# 13_ACODEC.net
KiCad netlist of a schematic drawn in Altium Designer
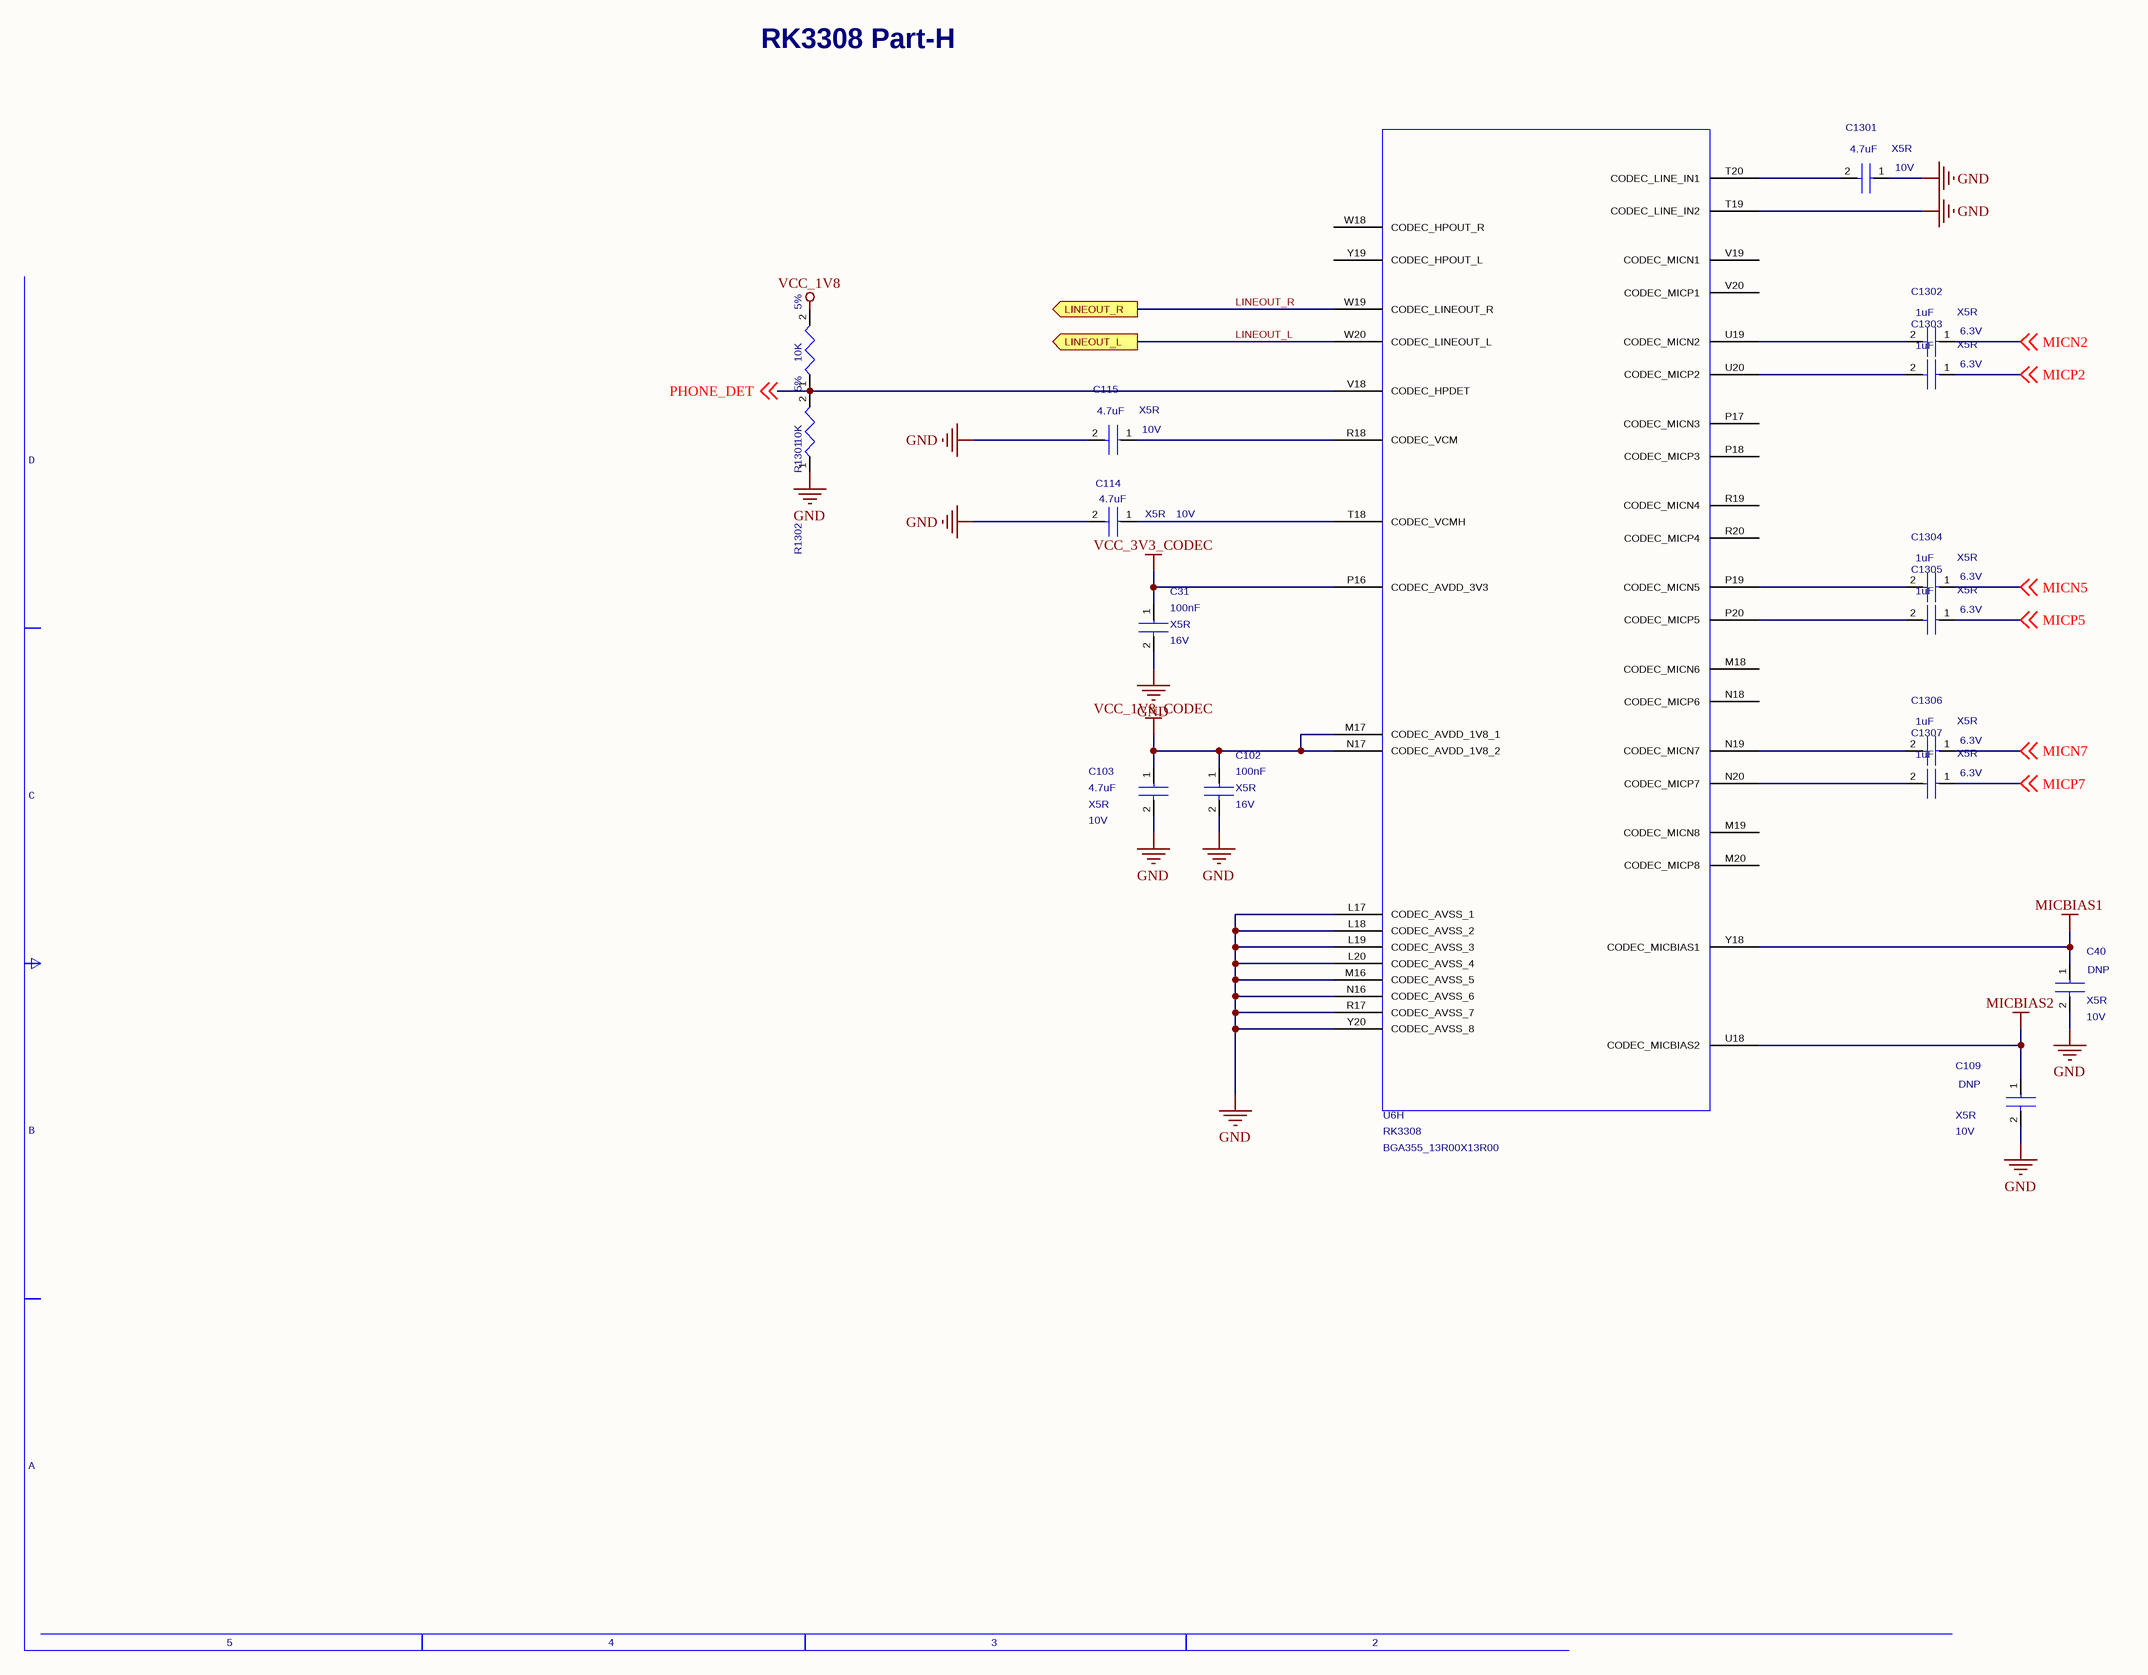
[diagram p0: 13_ACODEC.SchDoc]

(export (version "E")
  (design (tool "Eeschema 10.0.6"))
  (components
    (comp (ref "C31")
      (value "100nF")
      (footprint "C0402")
      (description "cap,100.00nF,+/-10%,16V,X5R,C0402")
      (fields
        (field (name "MANUFACTURER") "TDK")
        (field (name "TOLERANCE") "10%")
        (field (name "VOLTAGE") "16V")
        (field (name "DIELECTRIC") "X5R")
        (field (name "CREATED_BY") "JJJ")
      )
      (libsource (lib "*") (part "CAP_NP_2"))
    )
    (comp (ref "C40")
      (value "CAP_NP_2")
      (footprint "C0402")
      (description "cap,1.00uF,+/-10%,10V,X5R,C0402")
      (fields
        (field (name "DIELECTRIC") "X5R")
        (field (name "VOLTAGE") "10V")
        (field (name "TOLERANCE") "10%")
        (field (name "MANUFACTURER") "TDK")
        (field (name "OPTION") "DNP")
        (field (name "CREATED_BY") "JJJ")
      )
      (libsource (lib "*") (part "CAP_NP_2"))
    )
    (comp (ref "C102")
      (value "100nF")
      (footprint "C0402")
      (description "cap,100.00nF,+/-10%,16V,X5R,C0402")
      (fields
        (field (name "DIELECTRIC") "X5R")
        (field (name "VOLTAGE") "16V")
        (field (name "TOLERANCE") "10%")
        (field (name "MANUFACTURER") "TDK")
        (field (name "CREATED_BY") "JJJ")
      )
      (libsource (lib "*") (part "CAP_NP_2"))
    )
    (comp (ref "C103")
      (value "4.7uF")
      (footprint "C0402")
      (description "cap,4.70uF,+/-10%,10V,X5R,C0402")
      (fields
        (field (name "DIELECTRIC") "X5R")
        (field (name "VOLTAGE") "10V")
        (field (name "TOLERANCE") "10%")
        (field (name "MANUFACTURER") "TDK")
        (field (name "CREATED_BY") "JJJ")
      )
      (libsource (lib "*") (part "CAP_NP_2"))
    )
    (comp (ref "C109")
      (value "CAP_NP_2")
      (footprint "C0402")
      (description "cap,1.00uF,+/-10%,10V,X5R,C0402")
      (fields
        (field (name "MANUFACTURER") "TDK")
        (field (name "TOLERANCE") "10%")
        (field (name "VOLTAGE") "10V")
        (field (name "DIELECTRIC") "X5R")
        (field (name "OPTION") "DNP")
        (field (name "CREATED_BY") "JJJ")
      )
      (libsource (lib "*") (part "CAP_NP_2"))
    )
    (comp (ref "C114")
      (value "4.7uF")
      (footprint "C0603")
      (description "cap,4.70uF,+/-10%,10V,X5R,C0603")
      (fields
        (field (name "MANUFACTURER") "TDK")
        (field (name "TOLERANCE") "10%")
        (field (name "VOLTAGE") "10V")
        (field (name "DIELECTRIC") "X5R")
        (field (name "CREATED_BY") "JJJ")
      )
      (libsource (lib "*") (part "CAP_NP_2"))
    )
    (comp (ref "C115")
      (value "4.7uF")
      (footprint "C0603")
      (description "cap,4.70uF,+/-10%,10V,X5R,C0603")
      (fields
        (field (name "MANUFACTURER") "TDK")
        (field (name "TOLERANCE") "10%")
        (field (name "VOLTAGE") "10V")
        (field (name "DIELECTRIC") "X5R")
        (field (name "CREATED_BY") "JJJ")
      )
      (libsource (lib "*") (part "CAP_NP_2"))
    )
    (comp (ref "C1301")
      (value "4.7uF")
      (footprint "C0603")
      (description "cap,4.70uF,+/-10%,10V,X5R,C0603")
      (fields
        (field (name "MANUFACTURER") "TDK")
        (field (name "TOLERANCE") "10%")
        (field (name "VOLTAGE") "10V")
        (field (name "DIELECTRIC") "X5R")
        (field (name "CREATED_BY") "JJJ")
      )
      (libsource (lib "*") (part "CAP_NP_2"))
    )
    (comp (ref "C1302")
      (value "1uF")
      (footprint "C0402")
      (description "cap,1uF,+/-10%,10V,X5R,C0402")
      (fields
        (field (name "MANUFACTURER") "TDK")
        (field (name "TOLERANCE") "10%")
        (field (name "VOLTAGE") "6.3V")
        (field (name "DIELECTRIC") "X5R")
        (field (name "CREATED_BY") "JJJ")
      )
      (libsource (lib "*") (part "CAP_NP_2"))
    )
    (comp (ref "C1303")
      (value "1uF")
      (footprint "C0402")
      (description "cap,1uF,+/-10%,10V,X5R,C0402")
      (fields
        (field (name "MANUFACTURER") "TDK")
        (field (name "TOLERANCE") "10%")
        (field (name "VOLTAGE") "6.3V")
        (field (name "DIELECTRIC") "X5R")
        (field (name "CREATED_BY") "JJJ")
      )
      (libsource (lib "*") (part "CAP_NP_2"))
    )
    (comp (ref "C1304")
      (value "1uF")
      (footprint "C0402")
      (description "cap,1uF,+/-10%,10V,X5R,C0402")
      (fields
        (field (name "MANUFACTURER") "TDK")
        (field (name "TOLERANCE") "10%")
        (field (name "VOLTAGE") "6.3V")
        (field (name "DIELECTRIC") "X5R")
        (field (name "CREATED_BY") "JJJ")
      )
      (libsource (lib "*") (part "CAP_NP_2"))
    )
    (comp (ref "C1305")
      (value "1uF")
      (footprint "C0402")
      (description "cap,1uF,+/-10%,10V,X5R,C0402")
      (fields
        (field (name "MANUFACTURER") "TDK")
        (field (name "TOLERANCE") "10%")
        (field (name "VOLTAGE") "6.3V")
        (field (name "DIELECTRIC") "X5R")
        (field (name "CREATED_BY") "JJJ")
      )
      (libsource (lib "*") (part "CAP_NP_2"))
    )
    (comp (ref "C1306")
      (value "1uF")
      (footprint "C0402")
      (description "cap,1uF,+/-10%,10V,X5R,C0402")
      (fields
        (field (name "MANUFACTURER") "TDK")
        (field (name "TOLERANCE") "10%")
        (field (name "VOLTAGE") "6.3V")
        (field (name "DIELECTRIC") "X5R")
        (field (name "CREATED_BY") "JJJ")
      )
      (libsource (lib "*") (part "CAP_NP_2"))
    )
    (comp (ref "C1307")
      (value "1uF")
      (footprint "C0402")
      (description "cap,1uF,+/-10%,10V,X5R,C0402")
      (fields
        (field (name "MANUFACTURER") "TDK")
        (field (name "TOLERANCE") "10%")
        (field (name "VOLTAGE") "6.3V")
        (field (name "DIELECTRIC") "X5R")
        (field (name "CREATED_BY") "JJJ")
      )
      (libsource (lib "*") (part "CAP_NP_2"))
    )
    (comp (ref "R1301")
      (value "10K")
      (footprint "R0402")
      (description "?用厚膜电阻,2.2K,+/-5%,R0402,1/16W.")
      (fields
        (field (name "TOLERANCE") "5%")
        (field (name "MANUFACTURER") "YAGEO")
        (field (name "Comment") "RESISTOR")
        (field (name "CREATED_BY") "YTL")
      )
      (libsource (lib "*") (part "RESISTOR"))
    )
    (comp (ref "R1302")
      (value "10K")
      (footprint "R0402")
      (description "?用厚膜电阻,10K,+/-5%,R0402,1/16W.")
      (fields
        (field (name "TOLERANCE") "5%")
        (field (name "MANUFACTURER") "YAGEO")
        (field (name "Comment") "RESISTOR")
        (field (name "CREATED_BY") "YTL")
      )
      (libsource (lib "*") (part "RESISTOR"))
    )
    (comp (ref "U6")
      (value "RK3308")
      (footprint "BGA355_13R00X13R00")
      (fields (field (name "MANUFACTURER") "ROCKCHIP") (field (name "PCB DECAL") "BGA355_13R00X13R00"))
      (libsource (lib "RK3308SCH") (part "RK3308"))
    )
  )
  (nets
    (net (code "1") (name "/LINEOUT_L") (class "Default")
      (node (ref "U6") (pin "W20") (pinfunction "CODEC_LINEOUT_L_W20") (pintype "passive"))
    )
    (net (code "2") (name "/LINEOUT_R") (class "Default")
      (node (ref "U6") (pin "W19") (pinfunction "CODEC_LINEOUT_R_W19") (pintype "passive"))
    )
    (net (code "3") (name "GND") (class "Default")
      (node (ref "C102") (pin "2") (pinfunction "2_2") (pintype "passive"))
      (node (ref "C103") (pin "2") (pinfunction "2_2") (pintype "passive"))
      (node (ref "C109") (pin "2") (pinfunction "2_2") (pintype "passive"))
      (node (ref "C114") (pin "2") (pinfunction "2_2") (pintype "passive"))
      (node (ref "C115") (pin "2") (pinfunction "2_2") (pintype "passive"))
      (node (ref "C1301") (pin "1") (pinfunction "1_1") (pintype "passive"))
      (node (ref "C31") (pin "2") (pinfunction "2_2") (pintype "passive"))
      (node (ref "C40") (pin "2") (pinfunction "2_2") (pintype "passive"))
      (node (ref "R1302") (pin "1") (pinfunction "1_1") (pintype "passive"))
      (node (ref "U6") (pin "L17") (pinfunction "CODEC_AVSS_1_L17") (pintype "passive"))
      (node (ref "U6") (pin "L18") (pinfunction "CODEC_AVSS_2_L18") (pintype "passive"))
      (node (ref "U6") (pin "L19") (pinfunction "CODEC_AVSS_3_L19") (pintype "passive"))
      (node (ref "U6") (pin "L20") (pinfunction "CODEC_AVSS_4_L20") (pintype "passive"))
      (node (ref "U6") (pin "M16") (pinfunction "CODEC_AVSS_5_M16") (pintype "passive"))
      (node (ref "U6") (pin "N16") (pinfunction "CODEC_AVSS_6_N16") (pintype "passive"))
      (node (ref "U6") (pin "R17") (pinfunction "CODEC_AVSS_7_R17") (pintype "passive"))
      (node (ref "U6") (pin "T19") (pinfunction "CODEC_LINE_IN2_T19") (pintype "passive"))
      (node (ref "U6") (pin "Y20") (pinfunction "CODEC_AVSS_8_Y20") (pintype "passive"))
    )
    (net (code "4") (name "MICBIAS1") (class "Default")
      (node (ref "C40") (pin "1") (pinfunction "1_1") (pintype "passive"))
      (node (ref "U6") (pin "Y18") (pinfunction "CODEC_MICBIAS1_Y18") (pintype "passive"))
    )
    (net (code "5") (name "MICBIAS2") (class "Default")
      (node (ref "C109") (pin "1") (pinfunction "1_1") (pintype "passive"))
      (node (ref "U6") (pin "U18") (pinfunction "CODEC_MICBIAS2_U18") (pintype "passive"))
    )
    (net (code "6") (name "MICN2") (class "Default")
      (node (ref "C1302") (pin "1") (pinfunction "1_1") (pintype "passive"))
    )
    (net (code "7") (name "MICN5") (class "Default")
      (node (ref "C1304") (pin "1") (pinfunction "1_1") (pintype "passive"))
    )
    (net (code "8") (name "MICN7") (class "Default")
      (node (ref "C1306") (pin "1") (pinfunction "1_1") (pintype "passive"))
    )
    (net (code "9") (name "MICP2") (class "Default")
      (node (ref "C1303") (pin "1") (pinfunction "1_1") (pintype "passive"))
    )
    (net (code "10") (name "MICP5") (class "Default")
      (node (ref "C1305") (pin "1") (pinfunction "1_1") (pintype "passive"))
    )
    (net (code "11") (name "MICP7") (class "Default")
      (node (ref "C1307") (pin "1") (pinfunction "1_1") (pintype "passive"))
    )
    (net (code "12") (name "Net-(U6H-CODEC_LINE_IN1)") (class "Default")
      (node (ref "C1301") (pin "2") (pinfunction "2_2") (pintype "passive"))
      (node (ref "U6") (pin "T20") (pinfunction "CODEC_LINE_IN1_T20") (pintype "passive"))
    )
    (net (code "13") (name "Net-(U6H-CODEC_MICN2)") (class "Default")
      (node (ref "C1302") (pin "2") (pinfunction "2_2") (pintype "passive"))
      (node (ref "U6") (pin "U19") (pinfunction "CODEC_MICN2_U19") (pintype "passive"))
    )
    (net (code "14") (name "Net-(U6H-CODEC_MICN5)") (class "Default")
      (node (ref "C1304") (pin "2") (pinfunction "2_2") (pintype "passive"))
      (node (ref "U6") (pin "P19") (pinfunction "CODEC_MICN5_P19") (pintype "passive"))
    )
    (net (code "15") (name "Net-(U6H-CODEC_MICN7)") (class "Default")
      (node (ref "C1306") (pin "2") (pinfunction "2_2") (pintype "passive"))
      (node (ref "U6") (pin "N19") (pinfunction "CODEC_MICN7_N19") (pintype "passive"))
    )
    (net (code "16") (name "Net-(U6H-CODEC_MICP2)") (class "Default")
      (node (ref "C1303") (pin "2") (pinfunction "2_2") (pintype "passive"))
      (node (ref "U6") (pin "U20") (pinfunction "CODEC_MICP2_U20") (pintype "passive"))
    )
    (net (code "17") (name "Net-(U6H-CODEC_MICP5)") (class "Default")
      (node (ref "C1305") (pin "2") (pinfunction "2_2") (pintype "passive"))
      (node (ref "U6") (pin "P20") (pinfunction "CODEC_MICP5_P20") (pintype "passive"))
    )
    (net (code "18") (name "Net-(U6H-CODEC_MICP7)") (class "Default")
      (node (ref "C1307") (pin "2") (pinfunction "2_2") (pintype "passive"))
      (node (ref "U6") (pin "N20") (pinfunction "CODEC_MICP7_N20") (pintype "passive"))
    )
    (net (code "19") (name "Net-(U6H-CODEC_VCM)") (class "Default")
      (node (ref "C115") (pin "1") (pinfunction "1_1") (pintype "passive"))
      (node (ref "U6") (pin "R18") (pinfunction "CODEC_VCM_R18") (pintype "passive"))
    )
    (net (code "20") (name "Net-(U6H-CODEC_VCMH)") (class "Default")
      (node (ref "C114") (pin "1") (pinfunction "1_1") (pintype "passive"))
      (node (ref "U6") (pin "T18") (pinfunction "CODEC_VCMH_T18") (pintype "passive"))
    )
    (net (code "21") (name "PHONE_DET") (class "Default")
      (node (ref "R1301") (pin "1") (pinfunction "1_1") (pintype "passive"))
      (node (ref "R1302") (pin "2") (pinfunction "2_2") (pintype "passive"))
      (node (ref "U6") (pin "V18") (pinfunction "CODEC_HPDET_V18") (pintype "passive"))
    )
    (net (code "22") (name "VCC_1V8") (class "Default")
      (node (ref "R1301") (pin "2") (pinfunction "2_2") (pintype "passive"))
    )
    (net (code "23") (name "VCC_1V8_CODEC") (class "Default")
      (node (ref "C102") (pin "1") (pinfunction "1_1") (pintype "passive"))
      (node (ref "C103") (pin "1") (pinfunction "1_1") (pintype "passive"))
      (node (ref "U6") (pin "M17") (pinfunction "CODEC_AVDD_1V8_1_M17") (pintype "passive"))
      (node (ref "U6") (pin "N17") (pinfunction "CODEC_AVDD_1V8_2_N17") (pintype "passive"))
    )
    (net (code "24") (name "VCC_3V3_CODEC") (class "Default")
      (node (ref "C31") (pin "1") (pinfunction "1_1") (pintype "passive"))
      (node (ref "U6") (pin "P16") (pinfunction "CODEC_AVDD_3V3_P16") (pintype "passive"))
    )
    (net (code "25") (name "unconnected-(U6H-CODEC_HPOUT_L-PadY19)") (class "Default")
      (node (ref "U6") (pin "Y19") (pinfunction "CODEC_HPOUT_L_Y19") (pintype "passive"))
    )
    (net (code "26") (name "unconnected-(U6H-CODEC_HPOUT_R-PadW18)") (class "Default")
      (node (ref "U6") (pin "W18") (pinfunction "CODEC_HPOUT_R_W18") (pintype "passive"))
    )
    (net (code "27") (name "unconnected-(U6H-CODEC_MICN1-PadV19)") (class "Default")
      (node (ref "U6") (pin "V19") (pinfunction "CODEC_MICN1_V19") (pintype "passive"))
    )
    (net (code "28") (name "unconnected-(U6H-CODEC_MICN3-PadP17)") (class "Default")
      (node (ref "U6") (pin "P17") (pinfunction "CODEC_MICN3_P17") (pintype "passive"))
    )
    (net (code "29") (name "unconnected-(U6H-CODEC_MICN4-PadR19)") (class "Default")
      (node (ref "U6") (pin "R19") (pinfunction "CODEC_MICN4_R19") (pintype "passive"))
    )
    (net (code "30") (name "unconnected-(U6H-CODEC_MICN6-PadM18)") (class "Default")
      (node (ref "U6") (pin "M18") (pinfunction "CODEC_MICN6_M18") (pintype "passive"))
    )
    (net (code "31") (name "unconnected-(U6H-CODEC_MICN8-PadM19)") (class "Default")
      (node (ref "U6") (pin "M19") (pinfunction "CODEC_MICN8_M19") (pintype "passive"))
    )
    (net (code "32") (name "unconnected-(U6H-CODEC_MICP1-PadV20)") (class "Default")
      (node (ref "U6") (pin "V20") (pinfunction "CODEC_MICP1_V20") (pintype "passive"))
    )
    (net (code "33") (name "unconnected-(U6H-CODEC_MICP3-PadP18)") (class "Default")
      (node (ref "U6") (pin "P18") (pinfunction "CODEC_MICP3_P18") (pintype "passive"))
    )
    (net (code "34") (name "unconnected-(U6H-CODEC_MICP4-PadR20)") (class "Default")
      (node (ref "U6") (pin "R20") (pinfunction "CODEC_MICP4_R20") (pintype "passive"))
    )
    (net (code "35") (name "unconnected-(U6H-CODEC_MICP6-PadN18)") (class "Default")
      (node (ref "U6") (pin "N18") (pinfunction "CODEC_MICP6_N18") (pintype "passive"))
    )
    (net (code "36") (name "unconnected-(U6H-CODEC_MICP8-PadM20)") (class "Default")
      (node (ref "U6") (pin "M20") (pinfunction "CODEC_MICP8_M20") (pintype "passive"))
    )
  )
)
